# Connector_GTX.net
KiCad netlist of a schematic drawn in Altium Designer
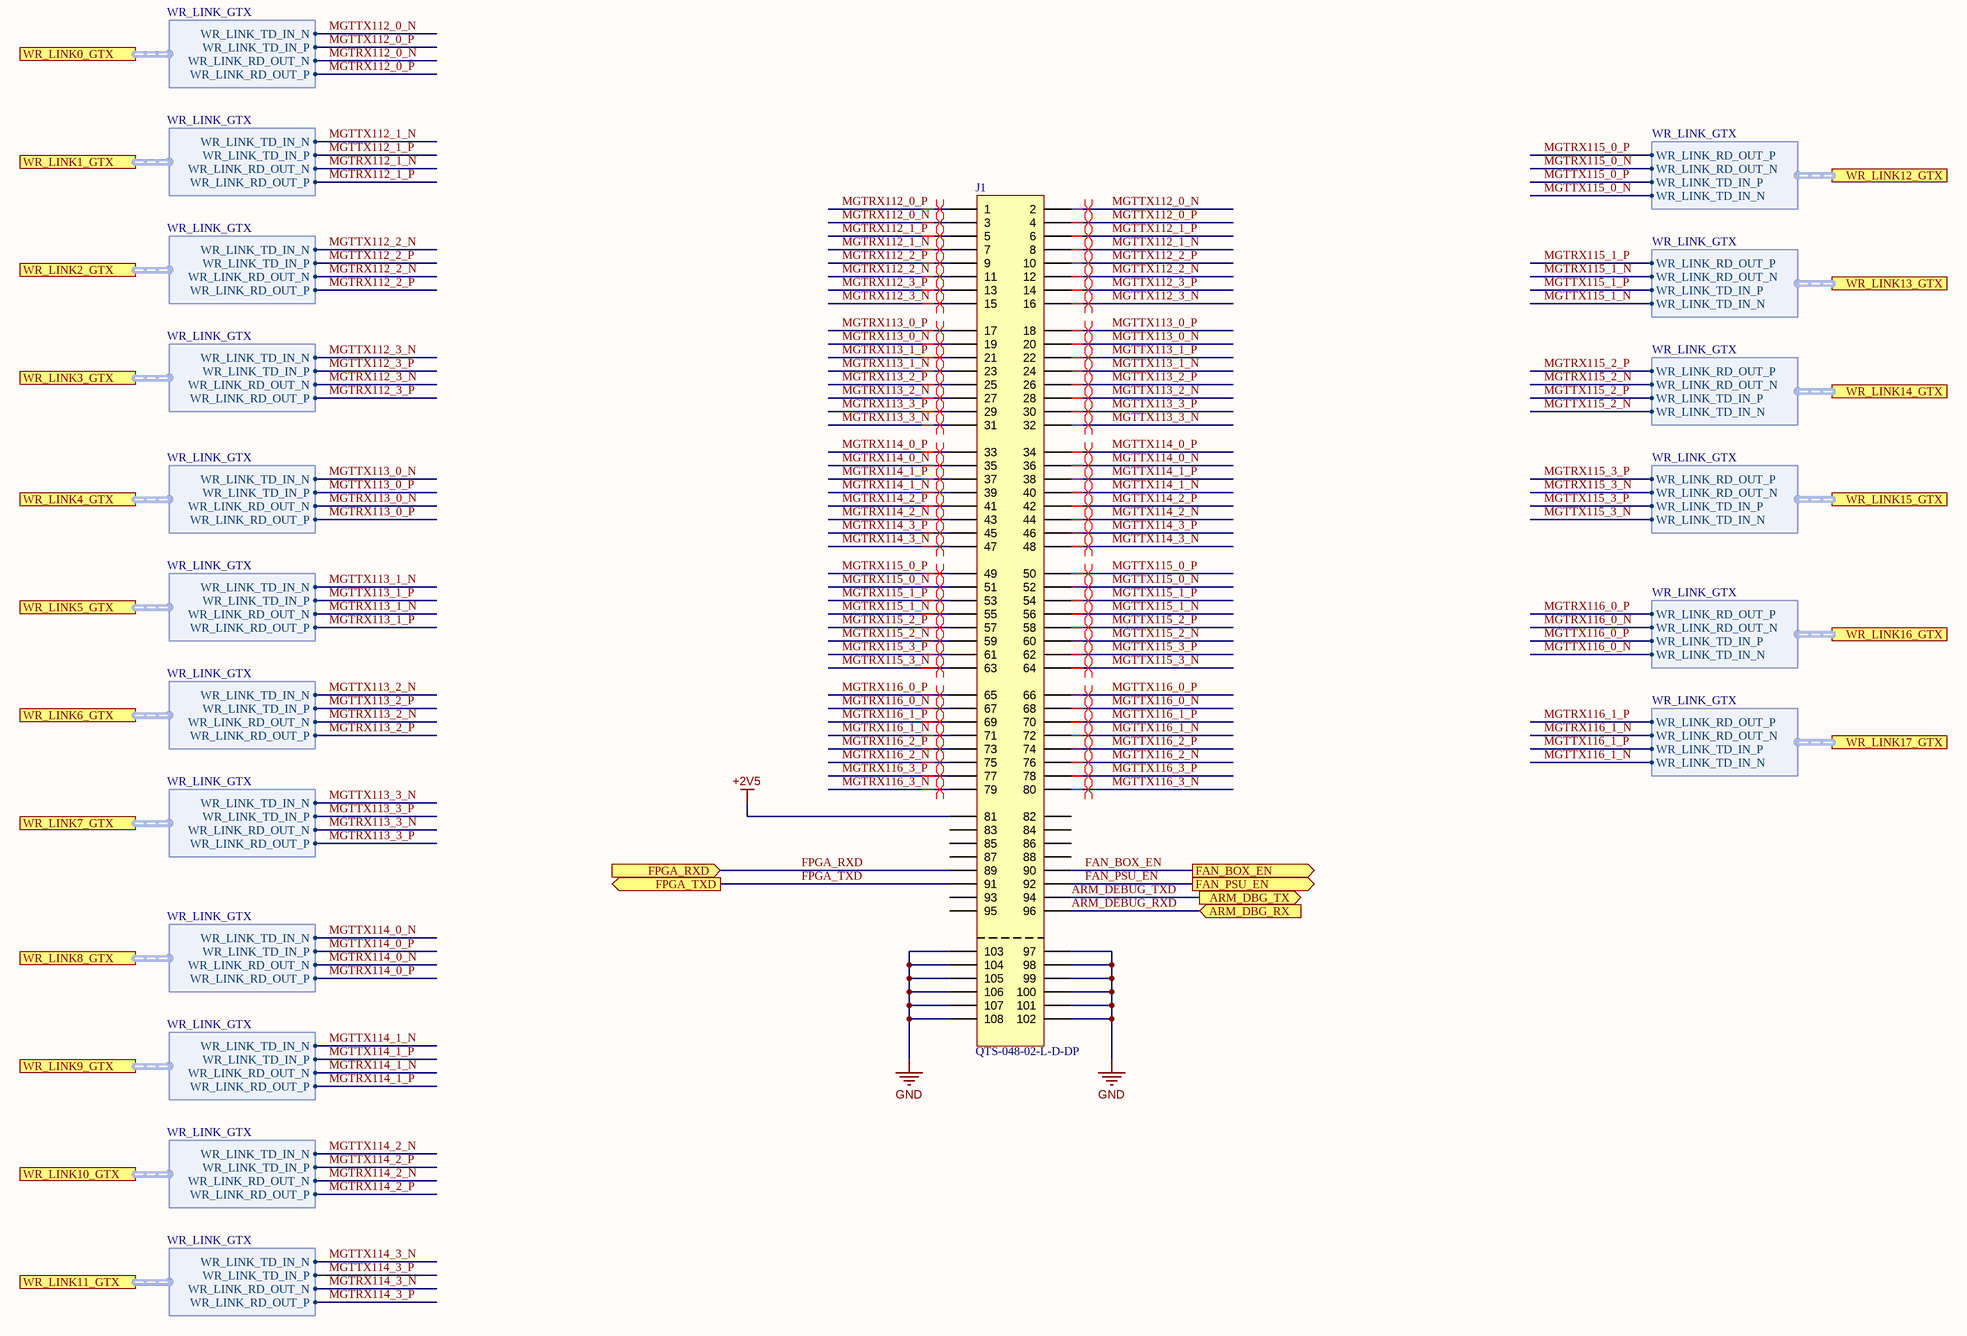
[diagram p0: Connector_GTX.SchDoc]

(export (version "E")
  (design (tool "Eeschema 10.0.6"))
  (components
    (comp (ref "J1")
      (value "QTS-048-02-L-D-DP")
      (footprint "7S_WR:QTS-048-XX-X-D-DP-A")
      (description "High Speed Ground Plane Header")
      (libsource (lib "wr_switch") (part "QTS-048-01-L-D-DP"))
    )
  )
  (nets
    (net (code "2") (name "+2V5") (class "Default")
      (node (ref "J1") (pin "81") (pinfunction "81_81") (pintype "passive"))
    )
    (net (code "3") (name "/ARM_DEBUG_RXD") (class "Default")
      (node (ref "J1") (pin "96") (pinfunction "96_96") (pintype "passive"))
    )
    (net (code "4") (name "/ARM_DEBUG_TXD") (class "Default")
      (node (ref "J1") (pin "94") (pinfunction "94_94") (pintype "passive"))
    )
    (net (code "5") (name "/FAN_BOX_EN") (class "Default")
      (node (ref "J1") (pin "90") (pinfunction "90_90") (pintype "passive"))
    )
    (net (code "6") (name "/FAN_PSU_EN") (class "Default")
      (node (ref "J1") (pin "92") (pinfunction "92_92") (pintype "passive"))
    )
    (net (code "7") (name "/FPGA_RXD") (class "Default")
      (node (ref "J1") (pin "89") (pinfunction "89_89") (pintype "passive"))
    )
    (net (code "8") (name "/FPGA_TXD") (class "Default")
      (node (ref "J1") (pin "91") (pinfunction "91_91") (pintype "passive"))
    )
    (net (code "9") (name "/MGTRX112_0_N") (class "Default")
      (node (ref "J1") (pin "3") (pinfunction "3_3") (pintype "passive"))
    )
    (net (code "10") (name "/MGTRX112_0_P") (class "Default")
      (node (ref "J1") (pin "1") (pinfunction "1_1") (pintype "passive"))
    )
    (net (code "11") (name "/MGTRX112_1_N") (class "Default")
      (node (ref "J1") (pin "7") (pinfunction "7_7") (pintype "passive"))
    )
    (net (code "12") (name "/MGTRX112_1_P") (class "Default")
      (node (ref "J1") (pin "5") (pinfunction "5_5") (pintype "passive"))
    )
    (net (code "13") (name "/MGTRX112_2_N") (class "Default")
      (node (ref "J1") (pin "11") (pinfunction "11_11") (pintype "passive"))
    )
    (net (code "14") (name "/MGTRX112_2_P") (class "Default")
      (node (ref "J1") (pin "9") (pinfunction "9_9") (pintype "passive"))
    )
    (net (code "15") (name "/MGTRX112_3_N") (class "Default")
      (node (ref "J1") (pin "15") (pinfunction "15_15") (pintype "passive"))
    )
    (net (code "16") (name "/MGTRX112_3_P") (class "Default")
      (node (ref "J1") (pin "13") (pinfunction "13_13") (pintype "passive"))
    )
    (net (code "17") (name "/MGTRX113_0_N") (class "Default")
      (node (ref "J1") (pin "19") (pinfunction "19_19") (pintype "passive"))
    )
    (net (code "18") (name "/MGTRX113_0_P") (class "Default")
      (node (ref "J1") (pin "17") (pinfunction "17_17") (pintype "passive"))
    )
    (net (code "19") (name "/MGTRX113_1_N") (class "Default")
      (node (ref "J1") (pin "23") (pinfunction "23_23") (pintype "passive"))
    )
    (net (code "20") (name "/MGTRX113_1_P") (class "Default")
      (node (ref "J1") (pin "21") (pinfunction "21_21") (pintype "passive"))
    )
    (net (code "21") (name "/MGTRX113_2_N") (class "Default")
      (node (ref "J1") (pin "27") (pinfunction "27_27") (pintype "passive"))
    )
    (net (code "22") (name "/MGTRX113_2_P") (class "Default")
      (node (ref "J1") (pin "25") (pinfunction "25_25") (pintype "passive"))
    )
    (net (code "23") (name "/MGTRX113_3_N") (class "Default")
      (node (ref "J1") (pin "31") (pinfunction "31_31") (pintype "passive"))
    )
    (net (code "24") (name "/MGTRX113_3_P") (class "Default")
      (node (ref "J1") (pin "29") (pinfunction "29_29") (pintype "passive"))
    )
    (net (code "25") (name "/MGTRX114_0_N") (class "Default")
      (node (ref "J1") (pin "35") (pinfunction "35_35") (pintype "passive"))
    )
    (net (code "26") (name "/MGTRX114_0_P") (class "Default")
      (node (ref "J1") (pin "33") (pinfunction "33_33") (pintype "passive"))
    )
    (net (code "27") (name "/MGTRX114_1_N") (class "Default")
      (node (ref "J1") (pin "39") (pinfunction "39_39") (pintype "passive"))
    )
    (net (code "28") (name "/MGTRX114_1_P") (class "Default")
      (node (ref "J1") (pin "37") (pinfunction "37_37") (pintype "passive"))
    )
    (net (code "29") (name "/MGTRX114_2_N") (class "Default")
      (node (ref "J1") (pin "43") (pinfunction "43_43") (pintype "passive"))
    )
    (net (code "30") (name "/MGTRX114_2_P") (class "Default")
      (node (ref "J1") (pin "41") (pinfunction "41_41") (pintype "passive"))
    )
    (net (code "31") (name "/MGTRX114_3_N") (class "Default")
      (node (ref "J1") (pin "47") (pinfunction "47_47") (pintype "passive"))
    )
    (net (code "32") (name "/MGTRX114_3_P") (class "Default")
      (node (ref "J1") (pin "45") (pinfunction "45_45") (pintype "passive"))
    )
    (net (code "33") (name "/MGTRX115_0_N") (class "Default")
      (node (ref "J1") (pin "51") (pinfunction "51_51") (pintype "passive"))
    )
    (net (code "34") (name "/MGTRX115_0_P") (class "Default")
      (node (ref "J1") (pin "49") (pinfunction "49_49") (pintype "passive"))
    )
    (net (code "35") (name "/MGTRX115_1_N") (class "Default")
      (node (ref "J1") (pin "55") (pinfunction "55_55") (pintype "passive"))
    )
    (net (code "36") (name "/MGTRX115_1_P") (class "Default")
      (node (ref "J1") (pin "53") (pinfunction "53_53") (pintype "passive"))
    )
    (net (code "37") (name "/MGTRX115_2_N") (class "Default")
      (node (ref "J1") (pin "59") (pinfunction "59_59") (pintype "passive"))
    )
    (net (code "38") (name "/MGTRX115_2_P") (class "Default")
      (node (ref "J1") (pin "57") (pinfunction "57_57") (pintype "passive"))
    )
    (net (code "39") (name "/MGTRX115_3_N") (class "Default")
      (node (ref "J1") (pin "63") (pinfunction "63_63") (pintype "passive"))
    )
    (net (code "40") (name "/MGTRX115_3_P") (class "Default")
      (node (ref "J1") (pin "61") (pinfunction "61_61") (pintype "passive"))
    )
    (net (code "41") (name "/MGTRX116_0_N") (class "Default")
      (node (ref "J1") (pin "67") (pinfunction "67_67") (pintype "passive"))
    )
    (net (code "42") (name "/MGTRX116_0_P") (class "Default")
      (node (ref "J1") (pin "65") (pinfunction "65_65") (pintype "passive"))
    )
    (net (code "43") (name "/MGTRX116_1_N") (class "Default")
      (node (ref "J1") (pin "71") (pinfunction "71_71") (pintype "passive"))
    )
    (net (code "44") (name "/MGTRX116_1_P") (class "Default")
      (node (ref "J1") (pin "69") (pinfunction "69_69") (pintype "passive"))
    )
    (net (code "45") (name "/MGTRX116_2_N") (class "Default")
      (node (ref "J1") (pin "75") (pinfunction "75_75") (pintype "passive"))
    )
    (net (code "46") (name "/MGTRX116_2_P") (class "Default")
      (node (ref "J1") (pin "73") (pinfunction "73_73") (pintype "passive"))
    )
    (net (code "47") (name "/MGTRX116_3_N") (class "Default")
      (node (ref "J1") (pin "79") (pinfunction "79_79") (pintype "passive"))
    )
    (net (code "48") (name "/MGTRX116_3_P") (class "Default")
      (node (ref "J1") (pin "77") (pinfunction "77_77") (pintype "passive"))
    )
    (net (code "49") (name "/MGTTX112_0_N") (class "Default")
      (node (ref "J1") (pin "2") (pinfunction "2_2") (pintype "passive"))
    )
    (net (code "50") (name "/MGTTX112_0_P") (class "Default")
      (node (ref "J1") (pin "4") (pinfunction "4_4") (pintype "passive"))
    )
    (net (code "51") (name "/MGTTX112_1_N") (class "Default")
      (node (ref "J1") (pin "8") (pinfunction "8_8") (pintype "passive"))
    )
    (net (code "52") (name "/MGTTX112_1_P") (class "Default")
      (node (ref "J1") (pin "6") (pinfunction "6_6") (pintype "passive"))
    )
    (net (code "53") (name "/MGTTX112_2_N") (class "Default")
      (node (ref "J1") (pin "12") (pinfunction "12_12") (pintype "passive"))
    )
    (net (code "54") (name "/MGTTX112_2_P") (class "Default")
      (node (ref "J1") (pin "10") (pinfunction "10_10") (pintype "passive"))
    )
    (net (code "55") (name "/MGTTX112_3_N") (class "Default")
      (node (ref "J1") (pin "16") (pinfunction "16_16") (pintype "passive"))
    )
    (net (code "56") (name "/MGTTX112_3_P") (class "Default")
      (node (ref "J1") (pin "14") (pinfunction "14_14") (pintype "passive"))
    )
    (net (code "57") (name "/MGTTX113_0_N") (class "Default")
      (node (ref "J1") (pin "20") (pinfunction "20_20") (pintype "passive"))
    )
    (net (code "58") (name "/MGTTX113_0_P") (class "Default")
      (node (ref "J1") (pin "18") (pinfunction "18_18") (pintype "passive"))
    )
    (net (code "59") (name "/MGTTX113_1_N") (class "Default")
      (node (ref "J1") (pin "24") (pinfunction "24_24") (pintype "passive"))
    )
    (net (code "60") (name "/MGTTX113_1_P") (class "Default")
      (node (ref "J1") (pin "22") (pinfunction "22_22") (pintype "passive"))
    )
    (net (code "61") (name "/MGTTX113_2_N") (class "Default")
      (node (ref "J1") (pin "28") (pinfunction "28_28") (pintype "passive"))
    )
    (net (code "62") (name "/MGTTX113_2_P") (class "Default")
      (node (ref "J1") (pin "26") (pinfunction "26_26") (pintype "passive"))
    )
    (net (code "63") (name "/MGTTX113_3_N") (class "Default")
      (node (ref "J1") (pin "32") (pinfunction "32_32") (pintype "passive"))
    )
    (net (code "64") (name "/MGTTX113_3_P") (class "Default")
      (node (ref "J1") (pin "30") (pinfunction "30_30") (pintype "passive"))
    )
    (net (code "65") (name "/MGTTX114_0_N") (class "Default")
      (node (ref "J1") (pin "36") (pinfunction "36_36") (pintype "passive"))
    )
    (net (code "66") (name "/MGTTX114_0_P") (class "Default")
      (node (ref "J1") (pin "34") (pinfunction "34_34") (pintype "passive"))
    )
    (net (code "67") (name "/MGTTX114_1_N") (class "Default")
      (node (ref "J1") (pin "40") (pinfunction "40_40") (pintype "passive"))
    )
    (net (code "68") (name "/MGTTX114_1_P") (class "Default")
      (node (ref "J1") (pin "38") (pinfunction "38_38") (pintype "passive"))
    )
    (net (code "69") (name "/MGTTX114_2_N") (class "Default")
      (node (ref "J1") (pin "44") (pinfunction "44_44") (pintype "passive"))
    )
    (net (code "70") (name "/MGTTX114_2_P") (class "Default")
      (node (ref "J1") (pin "42") (pinfunction "42_42") (pintype "passive"))
    )
    (net (code "71") (name "/MGTTX114_3_N") (class "Default")
      (node (ref "J1") (pin "48") (pinfunction "48_48") (pintype "passive"))
    )
    (net (code "72") (name "/MGTTX114_3_P") (class "Default")
      (node (ref "J1") (pin "46") (pinfunction "46_46") (pintype "passive"))
    )
    (net (code "73") (name "/MGTTX115_0_N") (class "Default")
      (node (ref "J1") (pin "52") (pinfunction "52_52") (pintype "passive"))
    )
    (net (code "74") (name "/MGTTX115_0_P") (class "Default")
      (node (ref "J1") (pin "50") (pinfunction "50_50") (pintype "passive"))
    )
    (net (code "75") (name "/MGTTX115_1_N") (class "Default")
      (node (ref "J1") (pin "56") (pinfunction "56_56") (pintype "passive"))
    )
    (net (code "76") (name "/MGTTX115_1_P") (class "Default")
      (node (ref "J1") (pin "54") (pinfunction "54_54") (pintype "passive"))
    )
    (net (code "77") (name "/MGTTX115_2_N") (class "Default")
      (node (ref "J1") (pin "60") (pinfunction "60_60") (pintype "passive"))
    )
    (net (code "78") (name "/MGTTX115_2_P") (class "Default")
      (node (ref "J1") (pin "58") (pinfunction "58_58") (pintype "passive"))
    )
    (net (code "79") (name "/MGTTX115_3_N") (class "Default")
      (node (ref "J1") (pin "64") (pinfunction "64_64") (pintype "passive"))
    )
    (net (code "80") (name "/MGTTX115_3_P") (class "Default")
      (node (ref "J1") (pin "62") (pinfunction "62_62") (pintype "passive"))
    )
    (net (code "81") (name "/MGTTX116_0_N") (class "Default")
      (node (ref "J1") (pin "68") (pinfunction "68_68") (pintype "passive"))
    )
    (net (code "82") (name "/MGTTX116_0_P") (class "Default")
      (node (ref "J1") (pin "66") (pinfunction "66_66") (pintype "passive"))
    )
    (net (code "83") (name "/MGTTX116_1_N") (class "Default")
      (node (ref "J1") (pin "72") (pinfunction "72_72") (pintype "passive"))
    )
    (net (code "84") (name "/MGTTX116_1_P") (class "Default")
      (node (ref "J1") (pin "70") (pinfunction "70_70") (pintype "passive"))
    )
    (net (code "85") (name "/MGTTX116_2_N") (class "Default")
      (node (ref "J1") (pin "76") (pinfunction "76_76") (pintype "passive"))
    )
    (net (code "86") (name "/MGTTX116_2_P") (class "Default")
      (node (ref "J1") (pin "74") (pinfunction "74_74") (pintype "passive"))
    )
    (net (code "87") (name "/MGTTX116_3_N") (class "Default")
      (node (ref "J1") (pin "80") (pinfunction "80_80") (pintype "passive"))
    )
    (net (code "88") (name "/MGTTX116_3_P") (class "Default")
      (node (ref "J1") (pin "78") (pinfunction "78_78") (pintype "passive"))
    )
    (net (code "90") (name "GND") (class "Default")
      (node (ref "J1") (pin "100") (pinfunction "100_100") (pintype "passive"))
      (node (ref "J1") (pin "101") (pinfunction "101_101") (pintype "passive"))
      (node (ref "J1") (pin "102") (pinfunction "102_102") (pintype "passive"))
      (node (ref "J1") (pin "103") (pinfunction "103_103") (pintype "passive"))
      (node (ref "J1") (pin "104") (pinfunction "104_104") (pintype "passive"))
      (node (ref "J1") (pin "105") (pinfunction "105_105") (pintype "passive"))
      (node (ref "J1") (pin "106") (pinfunction "106_106") (pintype "passive"))
      (node (ref "J1") (pin "107") (pinfunction "107_107") (pintype "passive"))
      (node (ref "J1") (pin "108") (pinfunction "108_108") (pintype "passive"))
      (node (ref "J1") (pin "97") (pinfunction "97_97") (pintype "passive"))
      (node (ref "J1") (pin "98") (pinfunction "98_98") (pintype "passive"))
      (node (ref "J1") (pin "99") (pinfunction "99_99") (pintype "passive"))
    )
    (net (code "91") (name "unconnected-(J1-Pad82)") (class "Default")
      (node (ref "J1") (pin "82") (pinfunction "82_82") (pintype "passive"))
    )
    (net (code "92") (name "unconnected-(J1-Pad83)") (class "Default")
      (node (ref "J1") (pin "83") (pinfunction "83_83") (pintype "passive"))
    )
    (net (code "93") (name "unconnected-(J1-Pad84)") (class "Default")
      (node (ref "J1") (pin "84") (pinfunction "84_84") (pintype "passive"))
    )
    (net (code "94") (name "unconnected-(J1-Pad85)") (class "Default")
      (node (ref "J1") (pin "85") (pinfunction "85_85") (pintype "passive"))
    )
    (net (code "95") (name "unconnected-(J1-Pad86)") (class "Default")
      (node (ref "J1") (pin "86") (pinfunction "86_86") (pintype "passive"))
    )
    (net (code "96") (name "unconnected-(J1-Pad87)") (class "Default")
      (node (ref "J1") (pin "87") (pinfunction "87_87") (pintype "passive"))
    )
    (net (code "97") (name "unconnected-(J1-Pad88)") (class "Default")
      (node (ref "J1") (pin "88") (pinfunction "88_88") (pintype "passive"))
    )
    (net (code "98") (name "unconnected-(J1-Pad93)") (class "Default")
      (node (ref "J1") (pin "93") (pinfunction "93_93") (pintype "passive"))
    )
    (net (code "99") (name "unconnected-(J1-Pad95)") (class "Default")
      (node (ref "J1") (pin "95") (pinfunction "95_95") (pintype "passive"))
    )
  )
)
